# 3V3_buck.net
KiCad netlist of a schematic drawn in Altium Designer
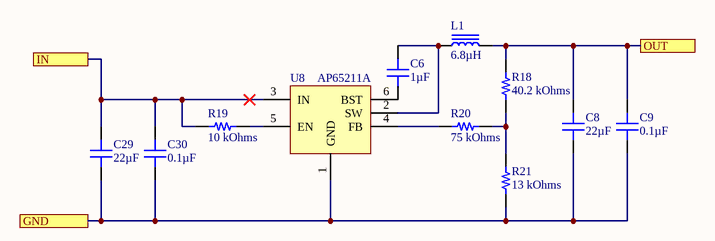
[diagram p0: 3V3_buck.SchDoc]

(export (version "E")
  (design (tool "Eeschema 10.0.6"))
  (components
    (comp (ref "C6")
      (value "1µF")
      (footprint "CAP 0402_1005")
      (description "CAP CER 0.1UF 35V X5R 0402")
      (fields
        (field (name "PART NUMBER") "CGA2B3X5R1V104K050BB")
        (field (name "MANUFACTURER") "TDK Corporation")
      )
      (libsource (lib "Celestial Altium Library - altium_library") (part "Capacitor"))
    )
    (comp (ref "C8")
      (value "22µF")
      (footprint "CAP 0402_1005")
      (description "CAP CER 0.1UF 35V X5R 0402")
      (fields
        (field (name "PART NUMBER") "CGA2B3X5R1V104K050BB")
        (field (name "MANUFACTURER") "TDK Corporation")
      )
      (libsource (lib "Celestial Altium Library - altium_library") (part "Capacitor"))
    )
    (comp (ref "C9")
      (value "0.1µF")
      (footprint "CAP 0402_1005")
      (description "CAP CER 0.1UF 35V X5R 0402")
      (fields
        (field (name "PART NUMBER") "CGA2B3X5R1V104K050BB")
        (field (name "MANUFACTURER") "TDK Corporation")
      )
      (libsource (lib "Celestial Altium Library - altium_library") (part "Capacitor"))
    )
    (comp (ref "C29")
      (value "22µF")
      (footprint "CAP 0402_1005")
      (description "CAP CER 0.1UF 35V X5R 0402")
      (fields
        (field (name "PART NUMBER") "CGA2B3X5R1V104K050BB")
        (field (name "MANUFACTURER") "TDK Corporation")
      )
      (libsource (lib "Celestial Altium Library - altium_library") (part "Capacitor"))
    )
    (comp (ref "C30")
      (value "0.1µF")
      (footprint "CAP 0402_1005")
      (description "CAP CER 0.1UF 35V X5R 0402")
      (fields
        (field (name "PART NUMBER") "CGA2B3X5R1V104K050BB")
        (field (name "MANUFACTURER") "TDK Corporation")
      )
      (libsource (lib "Celestial Altium Library - altium_library") (part "Capacitor"))
    )
    (comp (ref "L1")
      (value "6.8µH")
      (footprint "IND 0806_2016")
      (description "FIXED IND 6.8UH 910MA 468 MOHM")
      (fields
        (field (name "PART NUMBER") "VLS201612HBX-6R8M-1")
        (field (name "MANUFACTURER") "TDK Corporation")
      )
      (libsource (lib "Celestial Altium Library - altium_library") (part "Inductor"))
    )
    (comp (ref "R18")
      (value "40.2 kOhms")
      (footprint "RES 0402_1005")
      (description "RES SMD 1K OHM 5% 1/10W 0402")
      (fields
        (field (name "PART NUMBER") "ERJ-2GEJ102X")
        (field (name "MANUFACTURER") "Panasonic Electronic Components")
      )
      (libsource (lib "Celestial Altium Library - altium_library") (part "Resistor"))
    )
    (comp (ref "R19")
      (value "10 kOhms")
      (footprint "RES 0402_1005")
      (description "RES SMD 1K OHM 5% 1/10W 0402")
      (fields
        (field (name "PART NUMBER") "ERJ-2GEJ102X")
        (field (name "MANUFACTURER") "Panasonic Electronic Components")
      )
      (libsource (lib "Celestial Altium Library - altium_library") (part "Resistor"))
    )
    (comp (ref "R20")
      (value "75 kOhms")
      (footprint "RES 0402_1005")
      (description "RES SMD 1K OHM 5% 1/10W 0402")
      (fields
        (field (name "PART NUMBER") "ERJ-2GEJ102X")
        (field (name "MANUFACTURER") "Panasonic Electronic Components")
      )
      (libsource (lib "Celestial Altium Library - altium_library") (part "Resistor"))
    )
    (comp (ref "R21")
      (value "13 kOhms")
      (footprint "RES 0402_1005")
      (description "RES SMD 1K OHM 5% 1/10W 0402")
      (fields
        (field (name "PART NUMBER") "ERJ-2GEJ102X")
        (field (name "MANUFACTURER") "Panasonic Electronic Components")
      )
      (libsource (lib "Celestial Altium Library - altium_library") (part "Resistor"))
    )
    (comp (ref "U8")
      (value "AP65211A")
      (footprint "TSOT-26-6")
      (description "ADJ step down Buck")
      (libsource (lib "IC") (part "AP65211A"))
    )
  )
  (nets
    (net (code "1") (name "/GND") (class "Default")
      (node (ref "C29") (pin "1") (pinfunction "1_1") (pintype "passive"))
      (node (ref "C30") (pin "1") (pinfunction "1_1") (pintype "passive"))
      (node (ref "C8") (pin "1") (pinfunction "1_1") (pintype "passive"))
      (node (ref "C9") (pin "1") (pinfunction "1_1") (pintype "passive"))
      (node (ref "R21") (pin "1") (pinfunction "1_1") (pintype "passive"))
      (node (ref "U8") (pin "1") (pinfunction "GND_1") (pintype "passive"))
    )
    (net (code "2") (name "/IN") (class "Default")
      (node (ref "C29") (pin "2") (pinfunction "2_2") (pintype "passive"))
      (node (ref "C30") (pin "2") (pinfunction "2_2") (pintype "passive"))
      (node (ref "R19") (pin "1") (pinfunction "1_1") (pintype "passive"))
      (node (ref "U8") (pin "3") (pinfunction "IN_3") (pintype "passive"))
    )
    (net (code "3") (name "/OUT") (class "Default")
      (node (ref "C8") (pin "2") (pinfunction "2_2") (pintype "passive"))
      (node (ref "C9") (pin "2") (pinfunction "2_2") (pintype "passive"))
      (node (ref "L1") (pin "2") (pinfunction "2_2") (pintype "passive"))
      (node (ref "R18") (pin "2") (pinfunction "2_2") (pintype "passive"))
    )
    (net (code "4") (name "Net-(R18-Pad1)") (class "Default")
      (node (ref "R18") (pin "1") (pinfunction "1_1") (pintype "passive"))
      (node (ref "R20") (pin "2") (pinfunction "2_2") (pintype "passive"))
      (node (ref "R21") (pin "2") (pinfunction "2_2") (pintype "passive"))
    )
    (net (code "5") (name "Net-(U8-BST)") (class "Default")
      (node (ref "C6") (pin "1") (pinfunction "1_1") (pintype "passive"))
      (node (ref "U8") (pin "6") (pinfunction "BST_6") (pintype "passive"))
    )
    (net (code "6") (name "Net-(U8-EN)") (class "Default")
      (node (ref "R19") (pin "2") (pinfunction "2_2") (pintype "passive"))
      (node (ref "U8") (pin "5") (pinfunction "EN_5") (pintype "passive"))
    )
    (net (code "7") (name "Net-(U8-FB)") (class "Default")
      (node (ref "R20") (pin "1") (pinfunction "1_1") (pintype "passive"))
      (node (ref "U8") (pin "4") (pinfunction "FB_4") (pintype "passive"))
    )
    (net (code "8") (name "Net-(U8-SW)") (class "Default")
      (node (ref "C6") (pin "2") (pinfunction "2_2") (pintype "passive"))
      (node (ref "L1") (pin "1") (pinfunction "1_1") (pintype "passive"))
      (node (ref "U8") (pin "2") (pinfunction "SW_2") (pintype "passive"))
    )
  )
)
